# ProPrj_SX1262_125CM_v0_5_2026-09-01.net
KiCad netlist of a schematic drawn in EasyEDA Pro
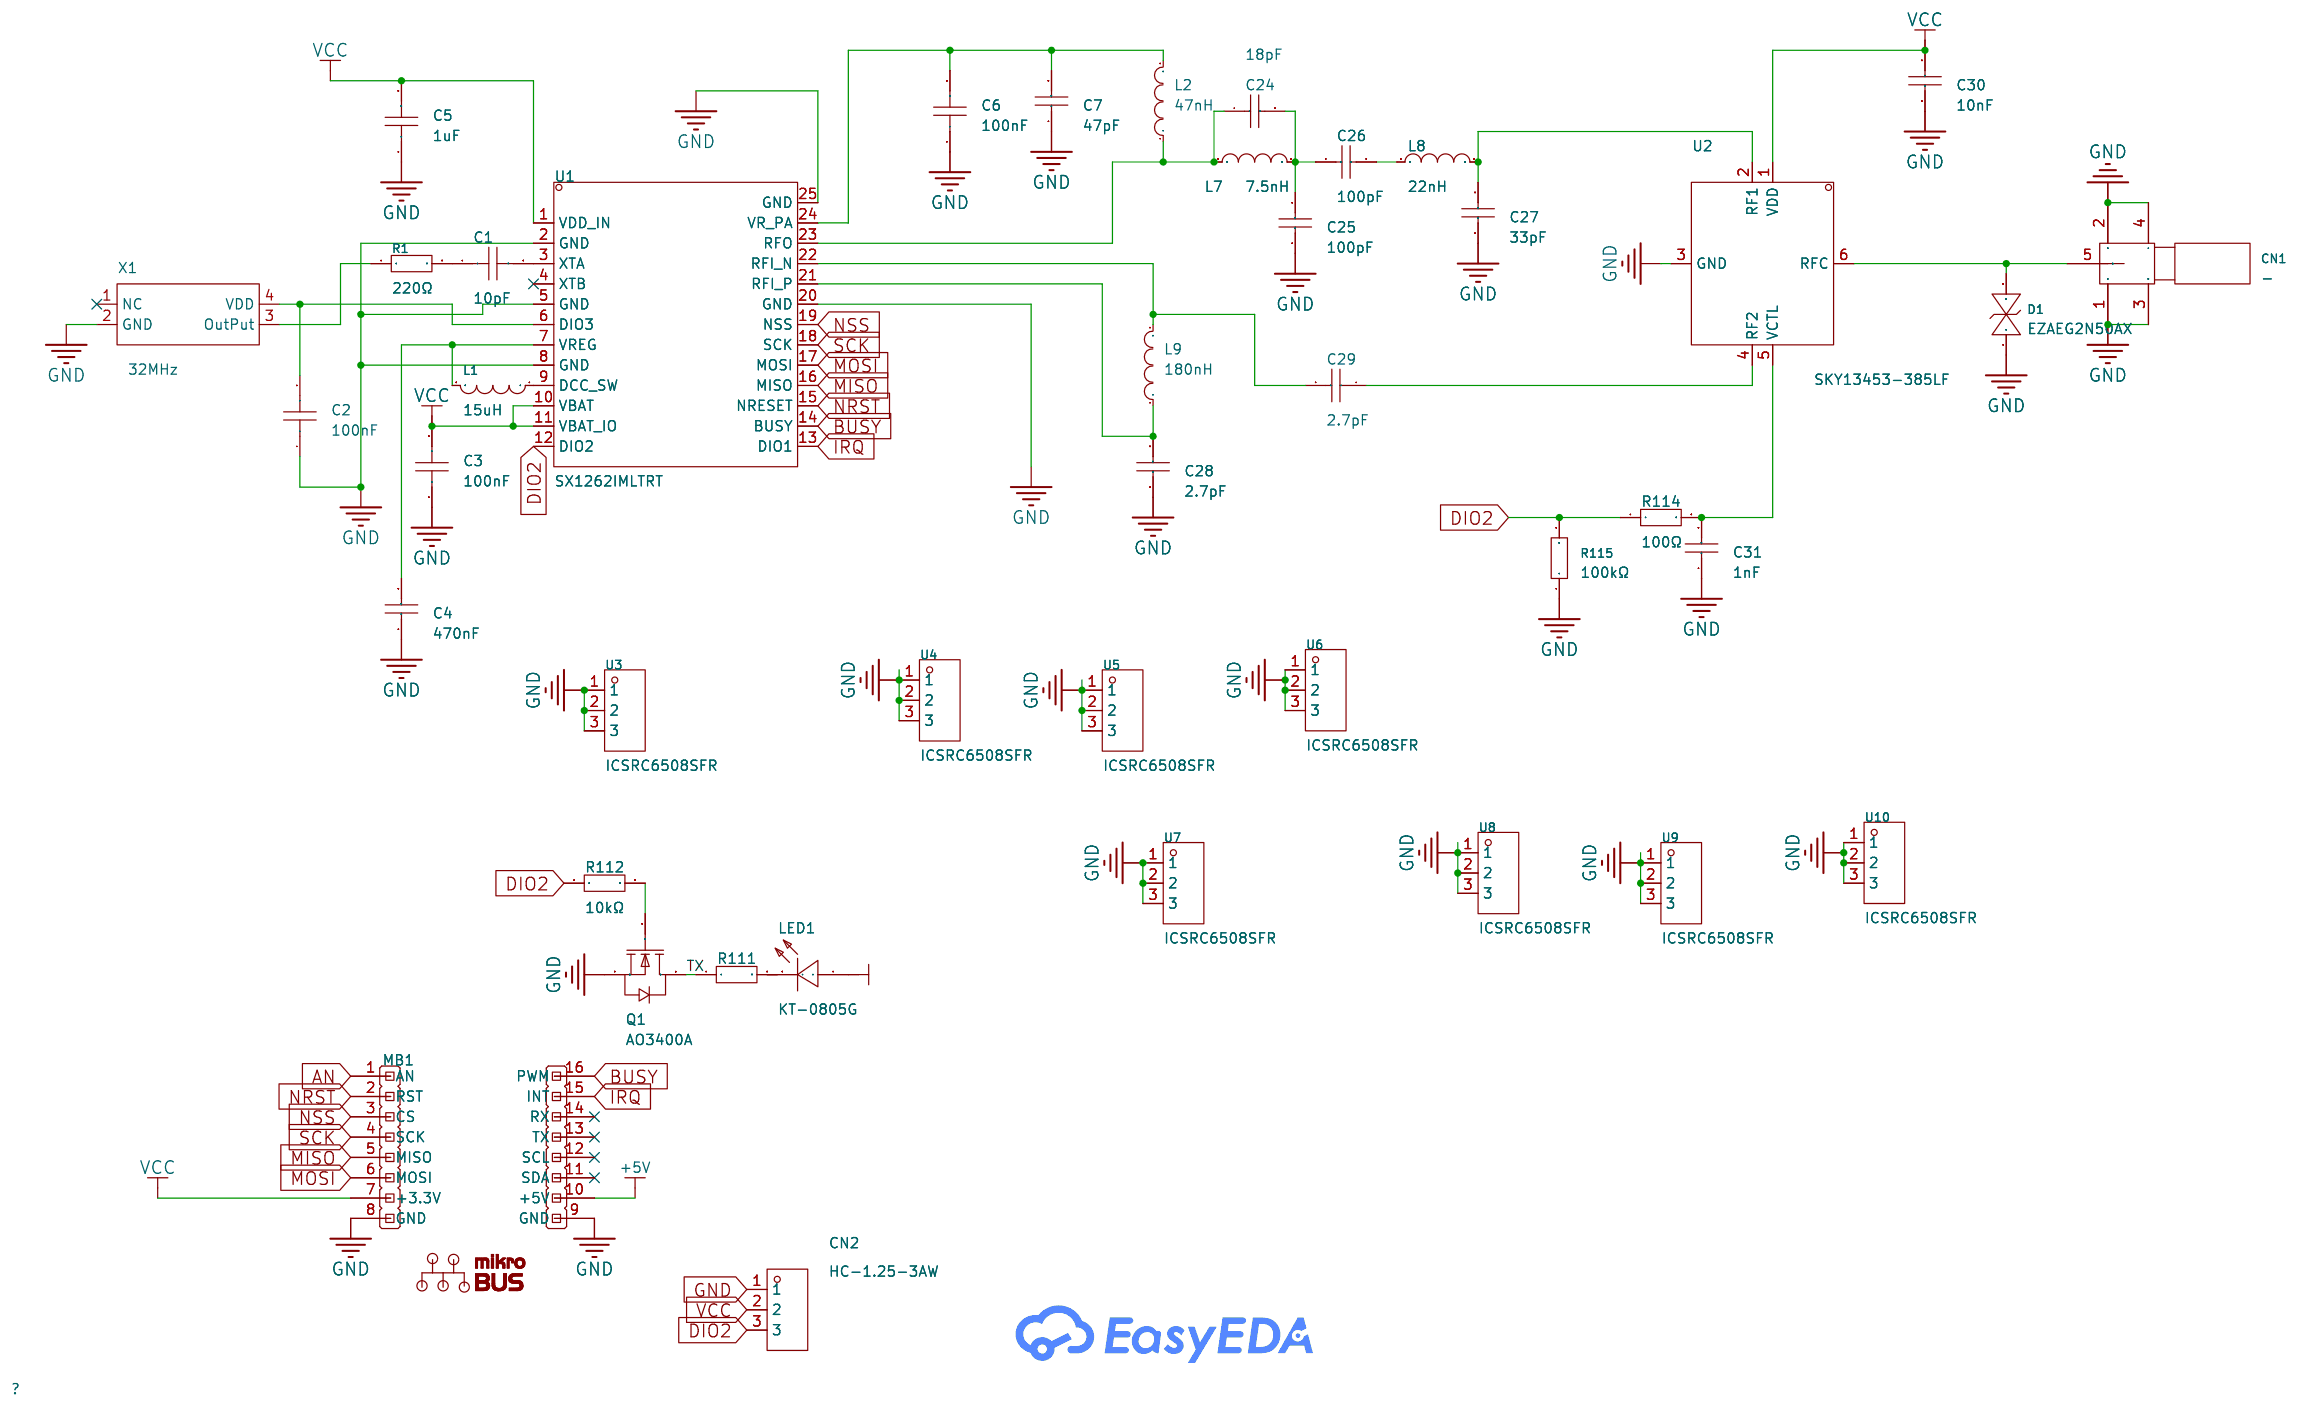
[diagram p0: schematic sheet]

(export (version "E")
  (design (tool "Eeschema 10.0.6"))
  (components
    (comp (ref "C1")
      (value "10pF")
      (footprint "easyedapro:C0402")
      (description "Capacitance:10pF Tolerance:±5% Tolerance:±5% Voltage Rating:50V Temperature Coefficient:C0G")
      (fields
        (field (name "Manufacturer Part") "CL05C100JB5NNNC")
        (field (name "Manufacturer") "SAMSUNG(三星)")
      )
      (libsource (lib "easyedapro") (part "CL05C100JB5NNNC"))
    )
    (comp (ref "C2")
      (value "100nF")
      (footprint "easyedapro:C0402")
      (description "Capacitance:100nF Tolerance:±10% Tolerance:±10% Voltage Rating:16V Temperature Coefficient:X7R")
      (fields
        (field (name "Manufacturer Part") "CL05B104KO5NNNC")
        (field (name "Manufacturer") "SAMSUNG(三星)")
      )
      (libsource (lib "easyedapro") (part "CL05B104KO5NNNC"))
    )
    (comp (ref "C3")
      (value "100nF")
      (footprint "easyedapro:C0402")
      (description "Capacitance:100nF Tolerance:±10% Tolerance:±10% Voltage Rating:16V Temperature Coefficient:X7R")
      (fields
        (field (name "Manufacturer Part") "CL05B104KO5NNNC")
        (field (name "Manufacturer") "SAMSUNG(三星)")
      )
      (libsource (lib "easyedapro") (part "CL05B104KO5NNNC"))
    )
    (comp (ref "C4")
      (value "470nF")
      (footprint "easyedapro:C0603")
      (description "Capacitance:470nF Tolerance:±10% Tolerance:±10% Voltage Rating:25V Temperature Coefficient:X7R")
      (fields
        (field (name "Manufacturer Part") "CL10B474KA8NNNC")
        (field (name "Manufacturer") "SAMSUNG(三星)")
      )
      (libsource (lib "easyedapro") (part "CL10B474KA8NNNC"))
    )
    (comp (ref "C5")
      (value "1uF")
      (footprint "easyedapro:C0402")
      (description "Capacitance:1uF Tolerance:±10% Tolerance:±10% Voltage Rating:25V Temperature Coefficient:X5R")
      (fields
        (field (name "Manufacturer Part") "CL05A105KA5NQNC")
        (field (name "Manufacturer") "SAMSUNG(三星)")
      )
      (libsource (lib "easyedapro") (part "CL05A105KA5NQNC"))
    )
    (comp (ref "C6")
      (value "100nF")
      (footprint "easyedapro:C0402")
      (description "Capacitance:100nF Tolerance:±10% Tolerance:±10% Voltage Rating:16V Temperature Coefficient:X7R")
      (fields
        (field (name "Manufacturer Part") "CL05B104KO5NNNC")
        (field (name "Manufacturer") "SAMSUNG(三星)")
      )
      (libsource (lib "easyedapro") (part "CL05B104KO5NNNC"))
    )
    (comp (ref "C7")
      (value "47pF")
      (footprint "easyedapro:C0402")
      (description "Capacitance:47pF Tolerance:±5% Tolerance:±5% Voltage Rating:50V Temperature Coefficient:C0G")
      (fields (field (name "Manufacturer Part") "0402CG470J500NT") (field (name "Manufacturer") "FH(风华)"))
      (libsource (lib "easyedapro") (part "0402CG470J500NT"))
    )
    (comp (ref "C24")
      (value "18pF")
      (footprint "easyedapro:C0402")
      (description "Capacitance:18pF Tolerance:±5% Tolerance:±5% Voltage Rating:50V Temperature Coefficient:C0G")
      (fields (field (name "Manufacturer Part") "0402CG180J500NT") (field (name "Manufacturer") "FH(风华)"))
      (libsource (lib "easyedapro") (part "0402CG330J500NT"))
    )
    (comp (ref "C25")
      (value "100pF")
      (footprint "easyedapro:C0402")
      (description "Capacitance:100pF Tolerance:±5% Tolerance:±5% Voltage Rating:50V Temperature Coefficient:C0G")
      (fields (field (name "Manufacturer Part") "0402CG101J500NT") (field (name "Manufacturer") "FH(风华)"))
      (libsource (lib "easyedapro") (part "GRM1555C1H8R2CA01D"))
    )
    (comp (ref "C26")
      (value "100pF")
      (footprint "easyedapro:C0402")
      (description "Capacitance:100pF Tolerance:±5% Tolerance:±5% Voltage Rating:50V Temperature Coefficient:C0G")
      (fields (field (name "Manufacturer Part") "0402CG101J500NT") (field (name "Manufacturer") "FH(风华)"))
      (libsource (lib "easyedapro") (part "0402CG4R7C500NT"))
    )
    (comp (ref "C27")
      (value "33pF")
      (footprint "easyedapro:C0402")
      (description "Capacitance:33pF Tolerance:±5% Tolerance:±5% Voltage Rating:50V Temperature Coefficient:C0G")
      (fields (field (name "Manufacturer Part") "0402CG330J500NT") (field (name "Manufacturer") "FH(风华)"))
      (libsource (lib "easyedapro") (part "0402CG120J500NT"))
    )
    (comp (ref "C28")
      (value "2.7pF")
      (footprint "easyedapro:C0402")
      (description "Capacitance:2.7pF Voltage Rating:50V Temperature Coefficient:C0G")
      (fields (field (name "Manufacturer Part") "0402CG2R7C500NT") (field (name "Manufacturer") "FH(风华)"))
      (libsource (lib "easyedapro") (part "0402CG180J500NT"))
    )
    (comp (ref "C29")
      (value "2.7pF")
      (footprint "easyedapro:C0402")
      (description "Capacitance:2.7pF Voltage Rating:50V Temperature Coefficient:C0G")
      (fields (field (name "Manufacturer Part") "0402CG2R7C500NT") (field (name "Manufacturer") "FH(风华)"))
      (libsource (lib "easyedapro") (part "0402CG180J500NT"))
    )
    (comp (ref "C30")
      (value "10nF")
      (footprint "easyedapro:C0402")
      (description "Capacitance:10nF Tolerance:±10% Tolerance:±10% Voltage Rating:50V Temperature Coefficient:X7R")
      (fields
        (field (name "Manufacturer Part") "CL05B103KB5NNNC")
        (field (name "Manufacturer") "SAMSUNG(三星)")
      )
      (libsource (lib "easyedapro") (part "0402B102K500NT"))
    )
    (comp (ref "C31")
      (value "1nF")
      (footprint "easyedapro:C0402")
      (description "Capacitance:1nF Tolerance:±10% Tolerance:±10% Voltage Rating:50V Temperature Coefficient:X7R")
      (fields (field (name "Manufacturer Part") "0402B102K500NT") (field (name "Manufacturer") "FH(风华)"))
      (libsource (lib "easyedapro") (part "0402B102K500NT"))
    )
    (comp (ref "CN1")
      (value "-")
      (footprint "easyedapro:CONN-SMD_KH-SMA-KE8-G")
      (fields (field (name "Manufacturer Part") "KH-SMA-KE8-G") (field (name "Manufacturer") "kinghelm(金航标)"))
      (libsource (lib "easyedapro") (part "KH-SMA-KE8-G"))
    )
    (comp (ref "CN2")
      (value "HC-1.25-3AW")
      (footprint "easyedapro:CONN-TH_3P-P1.25_HCTL_HC-1.25-3AW")
      (fields (field (name "Manufacturer") "HCTL(华灿天禄)"))
      (libsource (lib "easyedapro") (part "HC-1.25-3AW"))
    )
    (comp (ref "D1")
      (value "EZAEG2N50AX")
      (footprint "easyedapro:D0402-BI")
      (fields (field (name "Manufacturer") "PANASONIC(松下)"))
      (libsource (lib "easyedapro") (part "EZAEG2N50AX"))
    )
    (comp (ref "L1")
      (value "15uH")
      (footprint "easyedapro:L0805")
      (fields (field (name "Manufacturer Part") "MLZ2012M150WT000") (field (name "Manufacturer") "TDK"))
      (libsource (lib "easyedapro") (part "MLZ2012M150WT000"))
    )
    (comp (ref "L2")
      (value "47nH")
      (footprint "easyedapro:IND-SMD_L1.2-W0.6-1")
      (fields
        (field (name "Manufacturer Part") "SCW1005C47NJST")
        (field (name "Manufacturer") "Sunltech(顺磁)")
      )
      (libsource (lib "easyedapro") (part "SCW1005C47NJST"))
    )
    (comp (ref "L7")
      (value "7.5nH")
      (footprint "easyedapro:IND-SMD_L1.2-W0.7")
      (fields (field (name "Manufacturer Part") "LQG15HS7N5J02D") (field (name "Manufacturer") "muRata(村田)"))
      (libsource (lib "easyedapro") (part "AHW1005C-15NJTF"))
    )
    (comp (ref "L8")
      (value "22nH")
      (footprint "easyedapro:IND-SMD_L1.2-W0.7")
      (fields
        (field (name "Manufacturer Part") "SCW1005C22NJST")
        (field (name "Manufacturer") "Sunltech(顺磁)")
      )
      (libsource (lib "easyedapro") (part "AHW1005C-27NJTF"))
    )
    (comp (ref "L9")
      (value "180nH")
      (footprint "easyedapro:IND-SMD_L1.2-W0.6-1")
      (fields (field (name "Manufacturer Part") "MLG1005SR18JTD25") (field (name "Manufacturer") "TDK"))
      (libsource (lib "easyedapro") (part "SCW1005C68NJST"))
    )
    (comp (ref "LED1")
      (value "KT-0805G")
      (footprint "easyedapro:LED0805-R-RD")
      (fields (field (name "Manufacturer") "KENTO"))
      (libsource (lib "easyedapro") (part "0805G (Green)"))
    )
    (comp (ref "MB1")
      (value "~")
      (footprint "easyedapro:mikroBUS add-on Board")
      (description "ClickBoard")
      (libsource (lib "easyedapro") (part "mikroBUS"))
    )
    (comp (ref "Q1")
      (value "AO3400A")
      (footprint "easyedapro:SOT-23-3_L2.9-W1.3-P1.90-LS2.4-BR")
      (fields (field (name "Manufacturer") "AOS"))
      (libsource (lib "easyedapro") (part "AO3400A"))
    )
    (comp (ref "R1")
      (value "220Ω")
      (footprint "easyedapro:R0402")
      (fields
        (field (name "Manufacturer Part") "0402WGF2200TCE")
        (field (name "Manufacturer") "UNI-ROYAL(厚声)")
      )
      (libsource (lib "easyedapro") (part "0402WGF2200TCE"))
    )
    (comp (ref "R111")
      (value "470Ω")
      (footprint "easyedapro:R0402")
      (fields
        (field (name "Manufacturer Part") "0402WGF2200TCE")
        (field (name "Manufacturer") "UNI-ROYAL(厚声)")
      )
      (libsource (lib "easyedapro") (part "0402WGF2200TCE"))
    )
    (comp (ref "R112")
      (value "10kΩ")
      (footprint "easyedapro:R0402")
      (fields
        (field (name "Manufacturer Part") "0402WGF1002TCE")
        (field (name "Manufacturer") "UNI-ROYAL(厚声)")
      )
      (libsource (lib "easyedapro") (part "0402WGF1002TCE"))
    )
    (comp (ref "R114")
      (value "100Ω")
      (footprint "easyedapro:R0402")
      (fields
        (field (name "Manufacturer Part") "0402WGF1000TCE")
        (field (name "Manufacturer") "UNI-ROYAL(厚声)")
      )
      (libsource (lib "easyedapro") (part "0402WGF1000TCE"))
    )
    (comp (ref "R115")
      (value "100kΩ")
      (footprint "easyedapro:R0402")
      (fields
        (field (name "Manufacturer Part") "0402WGF1003TCE")
        (field (name "Manufacturer") "UNI-ROYAL(厚声)")
      )
      (libsource (lib "easyedapro") (part "0402WGF1003TCE"))
    )
    (comp (ref "U1")
      (value "SX1262IMLTRT")
      (footprint "easyedapro:QFN-24_L4.0-W4.0-P0.50-BL-EP2.6")
      (fields (field (name "Manufacturer") "SEMTECH"))
      (libsource (lib "easyedapro") (part "SX1262IMLTRT"))
    )
    (comp (ref "U2")
      (value "SKY13453-385LF")
      (footprint "easyedapro:QFN-6_L1.0-W1.0-P0.50-LS1.0-BL")
      (fields (field (name "Manufacturer") "SKYWORKS"))
      (libsource (lib "easyedapro") (part "SKY13453-385LF"))
    )
    (comp (ref "U3")
      (value "ICSRC6508SFR")
      (footprint "easyedapro:SMD_3P-L6.7-W0.9-R3-P2.65-ICSRC6508SFR")
      (description "size:6.5mm*1.21mm colour:White length:-")
      (fields (field (name "Manufacturer") "ICT"))
      (libsource (lib "easyedapro") (part "ICSRC6508SFR"))
    )
    (comp (ref "U4")
      (value "ICSRC6508SFR")
      (footprint "easyedapro:SMD_3P-L6.7-W0.9-R3-P2.65-ICSRC6508SFR")
      (description "size:6.5mm*1.21mm colour:White length:-")
      (fields (field (name "Manufacturer") "ICT"))
      (libsource (lib "easyedapro") (part "ICSRC6508SFR"))
    )
    (comp (ref "U5")
      (value "ICSRC6508SFR")
      (footprint "easyedapro:SMD_3P-L6.7-W0.9-R3-P2.65-ICSRC6508SFR")
      (description "size:6.5mm*1.21mm colour:White length:-")
      (fields (field (name "Manufacturer") "ICT"))
      (libsource (lib "easyedapro") (part "ICSRC6508SFR"))
    )
    (comp (ref "U6")
      (value "ICSRC6508SFR")
      (footprint "easyedapro:SMD_3P-L6.7-W0.9-R3-P2.65-ICSRC6508SFR")
      (description "size:6.5mm*1.21mm colour:White length:-")
      (fields (field (name "Manufacturer") "ICT"))
      (libsource (lib "easyedapro") (part "ICSRC6508SFR"))
    )
    (comp (ref "U7")
      (value "ICSRC6508SFR")
      (footprint "easyedapro:SMD_3P-L6.7-W0.9-R3-P2.65-ICSRC6508SFR")
      (description "size:6.5mm*1.21mm colour:White length:-")
      (fields (field (name "Manufacturer") "ICT"))
      (libsource (lib "easyedapro") (part "ICSRC6508SFR"))
    )
    (comp (ref "U8")
      (value "ICSRC6508SFR")
      (footprint "easyedapro:SMD_3P-L6.7-W0.9-R3-P2.65-ICSRC6508SFR")
      (description "size:6.5mm*1.21mm colour:White length:-")
      (fields (field (name "Manufacturer") "ICT"))
      (libsource (lib "easyedapro") (part "ICSRC6508SFR"))
    )
    (comp (ref "U9")
      (value "ICSRC6508SFR")
      (footprint "easyedapro:SMD_3P-L6.7-W0.9-R3-P2.65-ICSRC6508SFR")
      (description "size:6.5mm*1.21mm colour:White length:-")
      (fields (field (name "Manufacturer") "ICT"))
      (libsource (lib "easyedapro") (part "ICSRC6508SFR"))
    )
    (comp (ref "U10")
      (value "ICSRC6508SFR")
      (footprint "easyedapro:SMD_3P-L6.7-W0.9-R3-P2.65-ICSRC6508SFR")
      (description "size:6.5mm*1.21mm colour:White length:-")
      (fields (field (name "Manufacturer") "ICT"))
      (libsource (lib "easyedapro") (part "ICSRC6508SFR"))
    )
    (comp (ref "X1")
      (value "32MHz")
      (footprint "easyedapro:OSC-SMD_4P-L2.0-W1.6-BL_1")
      (fields
        (field (name "Manufacturer Part") "OW7EL89CANUXK7YLC-32M")
        (field (name "Manufacturer") "YXC(扬兴晶振)")
      )
      (libsource (lib "easyedapro") (part "OW7EL89CANUXK7YLC-32M"))
    )
  )
  (nets
    (net (code "1") (name "+5V") (class "Default")
      (node (ref "MB1") (pin "10") (pinfunction "+5V_10") (pintype "input"))
    )
    (net (code "2") (name "/TX") (class "Default")
      (node (ref "Q1") (pin "3") (pinfunction "D_3") (pintype "unspecified"))
      (node (ref "R111") (pin "1") (pinfunction "1_1") (pintype "input"))
    )
    (net (code "3") (name "AN") (class "Default")
      (node (ref "MB1") (pin "1") (pinfunction "AN_1") (pintype "input"))
    )
    (net (code "4") (name "BUSY") (class "Default")
      (node (ref "MB1") (pin "16") (pinfunction "PWM_16") (pintype "input"))
      (node (ref "U1") (pin "14") (pinfunction "BUSY_14") (pintype "unspecified"))
    )
    (net (code "5") (name "DIO2") (class "Default")
      (node (ref "CN2") (pin "3") (pinfunction "3_3") (pintype "unspecified"))
      (node (ref "R112") (pin "1") (pinfunction "1_1") (pintype "input"))
      (node (ref "R114") (pin "1") (pinfunction "1_1") (pintype "input"))
      (node (ref "R115") (pin "2") (pinfunction "2_2") (pintype "input"))
      (node (ref "U1") (pin "12") (pinfunction "DIO2_12") (pintype "unspecified"))
    )
    (net (code "6") (name "GND") (class "Default")
      (node (ref "C2") (pin "1") (pinfunction "1_1") (pintype "unspecified"))
      (node (ref "C25") (pin "1") (pinfunction "1_1") (pintype "input"))
      (node (ref "C27") (pin "1") (pinfunction "1_1") (pintype "input"))
      (node (ref "C28") (pin "1") (pinfunction "1_1") (pintype "input"))
      (node (ref "C3") (pin "1") (pinfunction "1_1") (pintype "unspecified"))
      (node (ref "C30") (pin "1") (pinfunction "1_1") (pintype "input"))
      (node (ref "C31") (pin "1") (pinfunction "1_1") (pintype "input"))
      (node (ref "C4") (pin "1") (pinfunction "1_1") (pintype "input"))
      (node (ref "C5") (pin "1") (pinfunction "1_1") (pintype "unspecified"))
      (node (ref "C6") (pin "1") (pinfunction "1_1") (pintype "unspecified"))
      (node (ref "C7") (pin "1") (pinfunction "1_1") (pintype "input"))
      (node (ref "CN1") (pin "1") (pinfunction "1_1") (pintype "unspecified"))
      (node (ref "CN1") (pin "2") (pinfunction "2_2") (pintype "unspecified"))
      (node (ref "CN1") (pin "3") (pinfunction "3_3") (pintype "unspecified"))
      (node (ref "CN1") (pin "4") (pinfunction "4_4") (pintype "unspecified"))
      (node (ref "CN2") (pin "1") (pinfunction "1_1") (pintype "unspecified"))
      (node (ref "D1") (pin "1") (pinfunction "1_1") (pintype "input"))
      (node (ref "MB1") (pin "8") (pinfunction "GND_8") (pintype "input"))
      (node (ref "MB1") (pin "9") (pinfunction "GND_9") (pintype "input"))
      (node (ref "Q1") (pin "2") (pinfunction "S_2") (pintype "unspecified"))
      (node (ref "R115") (pin "1") (pinfunction "1_1") (pintype "input"))
      (node (ref "U1") (pin "2") (pinfunction "GND_2") (pintype "unspecified"))
      (node (ref "U1") (pin "20") (pinfunction "GND_20") (pintype "unspecified"))
      (node (ref "U1") (pin "25") (pinfunction "GND_25") (pintype "unspecified"))
      (node (ref "U1") (pin "5") (pinfunction "GND_5") (pintype "unspecified"))
      (node (ref "U1") (pin "8") (pinfunction "GND_8") (pintype "unspecified"))
      (node (ref "U10") (pin "1") (pinfunction "1_1") (pintype "input"))
      (node (ref "U10") (pin "2") (pinfunction "2_2") (pintype "input"))
      (node (ref "U10") (pin "3") (pinfunction "3_3") (pintype "input"))
      (node (ref "U2") (pin "3") (pinfunction "GND_3") (pintype "unspecified"))
      (node (ref "U3") (pin "1") (pinfunction "1_1") (pintype "input"))
      (node (ref "U3") (pin "2") (pinfunction "2_2") (pintype "input"))
      (node (ref "U3") (pin "3") (pinfunction "3_3") (pintype "input"))
      (node (ref "U4") (pin "1") (pinfunction "1_1") (pintype "input"))
      (node (ref "U4") (pin "2") (pinfunction "2_2") (pintype "input"))
      (node (ref "U4") (pin "3") (pinfunction "3_3") (pintype "input"))
      (node (ref "U5") (pin "1") (pinfunction "1_1") (pintype "input"))
      (node (ref "U5") (pin "2") (pinfunction "2_2") (pintype "input"))
      (node (ref "U5") (pin "3") (pinfunction "3_3") (pintype "input"))
      (node (ref "U6") (pin "1") (pinfunction "1_1") (pintype "input"))
      (node (ref "U6") (pin "2") (pinfunction "2_2") (pintype "input"))
      (node (ref "U6") (pin "3") (pinfunction "3_3") (pintype "input"))
      (node (ref "U7") (pin "1") (pinfunction "1_1") (pintype "input"))
      (node (ref "U7") (pin "2") (pinfunction "2_2") (pintype "input"))
      (node (ref "U7") (pin "3") (pinfunction "3_3") (pintype "input"))
      (node (ref "U8") (pin "1") (pinfunction "1_1") (pintype "input"))
      (node (ref "U8") (pin "2") (pinfunction "2_2") (pintype "input"))
      (node (ref "U8") (pin "3") (pinfunction "3_3") (pintype "input"))
      (node (ref "U9") (pin "1") (pinfunction "1_1") (pintype "input"))
      (node (ref "U9") (pin "2") (pinfunction "2_2") (pintype "input"))
      (node (ref "U9") (pin "3") (pinfunction "3_3") (pintype "input"))
      (node (ref "X1") (pin "2") (pinfunction "GND_2") (pintype "unspecified"))
    )
    (net (code "7") (name "IRQ") (class "Default")
      (node (ref "MB1") (pin "15") (pinfunction "INT_15") (pintype "input"))
      (node (ref "U1") (pin "13") (pinfunction "DIO1_13") (pintype "unspecified"))
    )
    (net (code "8") (name "MISO") (class "Default")
      (node (ref "MB1") (pin "5") (pinfunction "MISO_5") (pintype "input"))
      (node (ref "U1") (pin "16") (pinfunction "MISO_16") (pintype "unspecified"))
    )
    (net (code "9") (name "MOSI") (class "Default")
      (node (ref "MB1") (pin "6") (pinfunction "MOSI_6") (pintype "input"))
      (node (ref "U1") (pin "17") (pinfunction "MOSI_17") (pintype "unspecified"))
    )
    (net (code "10") (name "NRST") (class "Default")
      (node (ref "MB1") (pin "2") (pinfunction "RST_2") (pintype "input"))
      (node (ref "U1") (pin "15") (pinfunction "NRESET_15") (pintype "unspecified"))
    )
    (net (code "11") (name "NSS") (class "Default")
      (node (ref "MB1") (pin "3") (pinfunction "CS_3") (pintype "input"))
      (node (ref "U1") (pin "19") (pinfunction "NSS_19") (pintype "unspecified"))
    )
    (net (code "12") (name "Net-(C1-Pad1)") (class "Default")
      (node (ref "C1") (pin "1") (pinfunction "1_1") (pintype "unspecified"))
      (node (ref "R1") (pin "2") (pinfunction "2_2") (pintype "input"))
    )
    (net (code "13") (name "Net-(C24-Pad2)") (class "Default")
      (node (ref "C24") (pin "2") (pinfunction "2_2") (pintype "input"))
      (node (ref "C25") (pin "2") (pinfunction "2_2") (pintype "input"))
      (node (ref "C26") (pin "1") (pinfunction "1_1") (pintype "input"))
      (node (ref "L7") (pin "2") (pinfunction "2_2") (pintype "unspecified"))
    )
    (net (code "14") (name "Net-(C26-Pad2)") (class "Default")
      (node (ref "C26") (pin "2") (pinfunction "2_2") (pintype "input"))
      (node (ref "L8") (pin "1") (pinfunction "1_1") (pintype "unspecified"))
    )
    (net (code "15") (name "Net-(LED1-K)") (class "Default")
      (node (ref "LED1") (pin "2") (pinfunction "K_2") (pintype "unspecified"))
      (node (ref "R111") (pin "2") (pinfunction "2_2") (pintype "input"))
    )
    (net (code "16") (name "Net-(Q1-G)") (class "Default")
      (node (ref "Q1") (pin "1") (pinfunction "G_1") (pintype "unspecified"))
      (node (ref "R112") (pin "2") (pinfunction "2_2") (pintype "input"))
    )
    (net (code "17") (name "Net-(U1-DCC_SW)") (class "Default")
      (node (ref "L1") (pin "1") (pinfunction "1_1") (pintype "input"))
      (node (ref "U1") (pin "9") (pinfunction "DCC_SW_9") (pintype "unspecified"))
    )
    (net (code "18") (name "Net-(U1-DIO3)") (class "Default")
      (node (ref "C2") (pin "2") (pinfunction "2_2") (pintype "unspecified"))
      (node (ref "U1") (pin "6") (pinfunction "DIO3_6") (pintype "unspecified"))
      (node (ref "X1") (pin "4") (pinfunction "VDD_4") (pintype "unspecified"))
    )
    (net (code "19") (name "Net-(U1-RFI_N)") (class "Default")
      (node (ref "C29") (pin "2") (pinfunction "2_2") (pintype "input"))
      (node (ref "L9") (pin "2") (pinfunction "2_2") (pintype "unspecified"))
      (node (ref "U1") (pin "22") (pinfunction "RFI_N_22") (pintype "unspecified"))
    )
    (net (code "20") (name "Net-(U1-RFI_P)") (class "Default")
      (node (ref "C28") (pin "2") (pinfunction "2_2") (pintype "input"))
      (node (ref "L9") (pin "1") (pinfunction "1_1") (pintype "unspecified"))
      (node (ref "U1") (pin "21") (pinfunction "RFI_P_21") (pintype "unspecified"))
    )
    (net (code "21") (name "Net-(U1-RFO)") (class "Default")
      (node (ref "C24") (pin "1") (pinfunction "1_1") (pintype "input"))
      (node (ref "L2") (pin "1") (pinfunction "1_1") (pintype "unspecified"))
      (node (ref "L7") (pin "1") (pinfunction "1_1") (pintype "unspecified"))
      (node (ref "U1") (pin "23") (pinfunction "RFO_23") (pintype "unspecified"))
    )
    (net (code "22") (name "Net-(U1-VREG)") (class "Default")
      (node (ref "C4") (pin "2") (pinfunction "2_2") (pintype "input"))
      (node (ref "L1") (pin "2") (pinfunction "2_2") (pintype "input"))
      (node (ref "U1") (pin "7") (pinfunction "VREG_7") (pintype "unspecified"))
    )
    (net (code "23") (name "Net-(U1-VR_PA)") (class "Default")
      (node (ref "C6") (pin "2") (pinfunction "2_2") (pintype "unspecified"))
      (node (ref "C7") (pin "2") (pinfunction "2_2") (pintype "input"))
      (node (ref "L2") (pin "2") (pinfunction "2_2") (pintype "unspecified"))
      (node (ref "U1") (pin "24") (pinfunction "VR_PA_24") (pintype "unspecified"))
    )
    (net (code "24") (name "Net-(U1-XTA)") (class "Default")
      (node (ref "C1") (pin "2") (pinfunction "2_2") (pintype "unspecified"))
      (node (ref "U1") (pin "3") (pinfunction "XTA_3") (pintype "unspecified"))
    )
    (net (code "25") (name "Net-(U2-RF1)") (class "Default")
      (node (ref "C27") (pin "2") (pinfunction "2_2") (pintype "input"))
      (node (ref "L8") (pin "2") (pinfunction "2_2") (pintype "unspecified"))
      (node (ref "U2") (pin "2") (pinfunction "RF1_2") (pintype "unspecified"))
    )
    (net (code "26") (name "Net-(U2-RF2)") (class "Default")
      (node (ref "C29") (pin "1") (pinfunction "1_1") (pintype "input"))
      (node (ref "U2") (pin "4") (pinfunction "RF2_4") (pintype "unspecified"))
    )
    (net (code "27") (name "Net-(U2-RFC)") (class "Default")
      (node (ref "CN1") (pin "5") (pinfunction "5_5") (pintype "unspecified"))
      (node (ref "D1") (pin "2") (pinfunction "2_2") (pintype "input"))
      (node (ref "U2") (pin "6") (pinfunction "RFC_6") (pintype "unspecified"))
    )
    (net (code "28") (name "Net-(U2-VCTL)") (class "Default")
      (node (ref "C31") (pin "2") (pinfunction "2_2") (pintype "input"))
      (node (ref "R114") (pin "2") (pinfunction "2_2") (pintype "input"))
      (node (ref "U2") (pin "5") (pinfunction "VCTL_5") (pintype "unspecified"))
    )
    (net (code "29") (name "Net-(X1-OutPut)") (class "Default")
      (node (ref "R1") (pin "1") (pinfunction "1_1") (pintype "input"))
      (node (ref "X1") (pin "3") (pinfunction "OutPut_3") (pintype "unspecified"))
    )
    (net (code "30") (name "SCK") (class "Default")
      (node (ref "MB1") (pin "4") (pinfunction "SCK_4") (pintype "input"))
      (node (ref "U1") (pin "18") (pinfunction "SCK_18") (pintype "unspecified"))
    )
    (net (code "31") (name "VCC") (class "Default")
      (node (ref "C3") (pin "2") (pinfunction "2_2") (pintype "unspecified"))
      (node (ref "C30") (pin "2") (pinfunction "2_2") (pintype "input"))
      (node (ref "C5") (pin "2") (pinfunction "2_2") (pintype "unspecified"))
      (node (ref "CN2") (pin "2") (pinfunction "2_2") (pintype "unspecified"))
      (node (ref "LED1") (pin "1") (pinfunction "A_1") (pintype "unspecified"))
      (node (ref "MB1") (pin "7") (pinfunction "+3.3V_7") (pintype "input"))
      (node (ref "U1") (pin "1") (pinfunction "VDD_IN_1") (pintype "unspecified"))
      (node (ref "U1") (pin "10") (pinfunction "VBAT_10") (pintype "unspecified"))
      (node (ref "U1") (pin "11") (pinfunction "VBAT_IO_11") (pintype "unspecified"))
      (node (ref "U2") (pin "1") (pinfunction "VDD_1") (pintype "unspecified"))
    )
    (net (code "32") (name "unconnected-(MB1-RX-Pad14)") (class "Default")
      (node (ref "MB1") (pin "14") (pinfunction "RX_14") (pintype "input+no_connect"))
    )
    (net (code "33") (name "unconnected-(MB1-SCL-Pad12)") (class "Default")
      (node (ref "MB1") (pin "12") (pinfunction "SCL_12") (pintype "input+no_connect"))
    )
    (net (code "34") (name "unconnected-(MB1-SDA-Pad11)") (class "Default")
      (node (ref "MB1") (pin "11") (pinfunction "SDA_11") (pintype "input+no_connect"))
    )
    (net (code "35") (name "unconnected-(MB1-TX-Pad13)") (class "Default")
      (node (ref "MB1") (pin "13") (pinfunction "TX_13") (pintype "input+no_connect"))
    )
    (net (code "36") (name "unconnected-(U1-XTB-Pad4)") (class "Default")
      (node (ref "U1") (pin "4") (pinfunction "XTB_4") (pintype "unspecified+no_connect"))
    )
    (net (code "37") (name "unconnected-(X1-NC-Pad1)") (class "Default")
      (node (ref "X1") (pin "1") (pinfunction "NC_1") (pintype "unspecified+no_connect"))
    )
  )
)
